# TriggerAndCVs_connectors.net
KiCad netlist of a schematic drawn in EAGLE
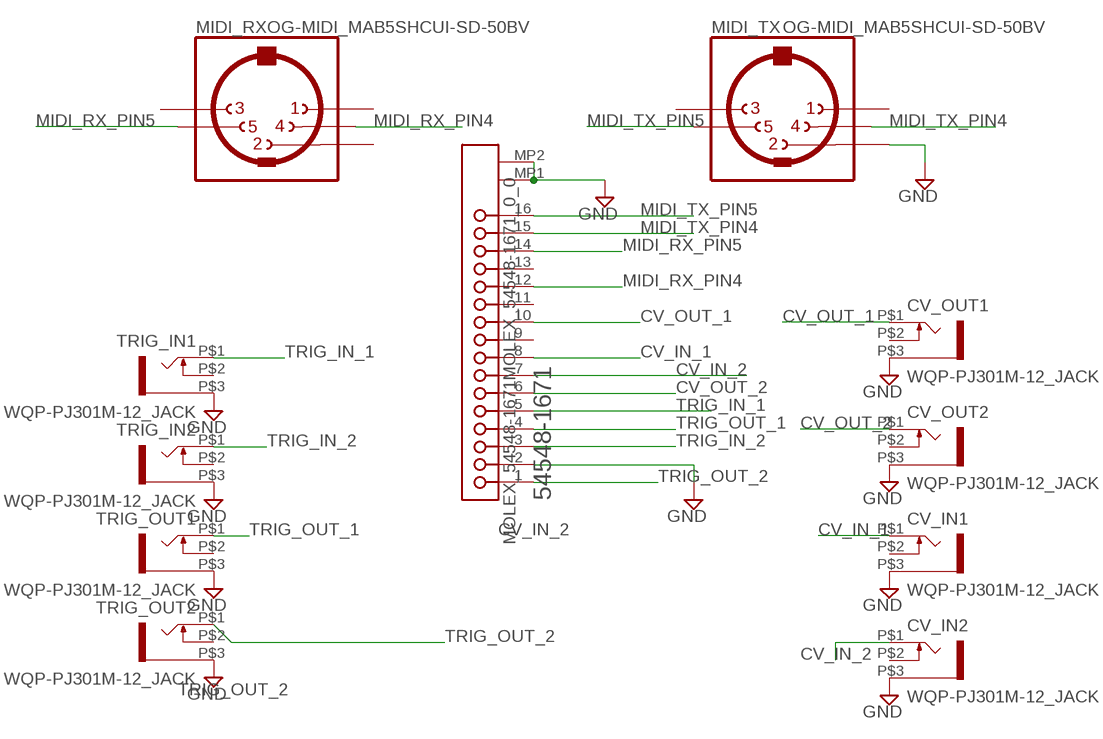
[diagram p0: schematic, sheet 1]

(export (version "E")
  (design (tool "Eeschema 10.0.6"))
  (components
    (comp (ref "CV_IN1")
      (value "WQP-PJ301M-12_JACK")
      (footprint "eagle-import:WQP-PJ301M-12_JACK")
      (libsource (lib "eagle-import") (part "WQP-PJ301M-12_JACK"))
    )
    (comp (ref "CV_IN2")
      (value "WQP-PJ301M-12_JACK")
      (footprint "eagle-import:WQP-PJ301M-12_JACK")
      (libsource (lib "eagle-import") (part "WQP-PJ301M-12_JACK"))
    )
    (comp (ref "CV_OUT1")
      (value "WQP-PJ301M-12_JACK")
      (footprint "eagle-import:WQP-PJ301M-12_JACK")
      (libsource (lib "eagle-import") (part "WQP-PJ301M-12_JACK"))
    )
    (comp (ref "CV_OUT2")
      (value "WQP-PJ301M-12_JACK")
      (footprint "eagle-import:WQP-PJ301M-12_JACK")
      (libsource (lib "eagle-import") (part "WQP-PJ301M-12_JACK"))
    )
    (comp (ref "JP4")
      (value "MOLEX_54548-1671MOLEX_54548-1671_0_0")
      (footprint "eagle-import:MOLEX_54548-1671_0")
      (fields (field (name "MF") "Molex") (field (name "MPN") "54548-1671"))
      (libsource (lib "eagle-import") (part "MOLEX_54548-1671MOLEX_54548-1671_0_0"))
    )
    (comp (ref "MIDI_RX")
      (value "OG-MIDI_MAB5SHCUI-SD-50BV")
      (footprint "eagle-import:OG-MIDI_SD-50BV")
      (libsource (lib "eagle-import") (part "OG-MIDI_MAB5SHCUI-SD-50BV"))
    )
    (comp (ref "MIDI_TX")
      (value "OG-MIDI_MAB5SHCUI-SD-50BV")
      (footprint "eagle-import:OG-MIDI_SD-50BV")
      (libsource (lib "eagle-import") (part "OG-MIDI_MAB5SHCUI-SD-50BV"))
    )
    (comp (ref "TRIG_IN1")
      (value "WQP-PJ301M-12_JACK")
      (footprint "eagle-import:WQP-PJ301M-12_JACK")
      (libsource (lib "eagle-import") (part "WQP-PJ301M-12_JACK"))
    )
    (comp (ref "TRIG_IN2")
      (value "WQP-PJ301M-12_JACK")
      (footprint "eagle-import:WQP-PJ301M-12_JACK")
      (libsource (lib "eagle-import") (part "WQP-PJ301M-12_JACK"))
    )
    (comp (ref "TRIG_OUT1")
      (value "WQP-PJ301M-12_JACK")
      (footprint "eagle-import:WQP-PJ301M-12_JACK")
      (libsource (lib "eagle-import") (part "WQP-PJ301M-12_JACK"))
    )
    (comp (ref "TRIG_OUT2")
      (value "WQP-PJ301M-12_JACK")
      (footprint "eagle-import:WQP-PJ301M-12_JACK")
      (libsource (lib "eagle-import") (part "WQP-PJ301M-12_JACK"))
    )
  )
  (nets
    (net (code "1") (name "/CV_IN_1") (class "Default")
      (node (ref "CV_IN1") (pin "P$1") (pinfunction "2_P$1") (pintype "passive"))
      (node (ref "JP4") (pin "8") (pinfunction "8_8") (pintype "passive"))
    )
    (net (code "2") (name "/CV_IN_2") (class "Default")
      (node (ref "CV_IN2") (pin "P$1") (pinfunction "2_P$1") (pintype "passive"))
      (node (ref "JP4") (pin "7") (pinfunction "7_7") (pintype "passive"))
    )
    (net (code "3") (name "/CV_OUT_1") (class "Default")
      (node (ref "CV_OUT1") (pin "P$1") (pinfunction "2_P$1") (pintype "passive"))
      (node (ref "JP4") (pin "10") (pinfunction "10_10") (pintype "passive"))
    )
    (net (code "4") (name "/CV_OUT_2") (class "Default")
      (node (ref "CV_OUT2") (pin "P$1") (pinfunction "2_P$1") (pintype "passive"))
      (node (ref "JP4") (pin "6") (pinfunction "6_6") (pintype "passive"))
    )
    (net (code "5") (name "/MIDI_RX_PIN4") (class "Default")
      (node (ref "JP4") (pin "12") (pinfunction "12_12") (pintype "passive"))
      (node (ref "MIDI_RX") (pin "4") (pinfunction "4_4") (pintype "passive"))
    )
    (net (code "6") (name "/MIDI_RX_PIN5") (class "Default")
      (node (ref "JP4") (pin "14") (pinfunction "14_14") (pintype "passive"))
      (node (ref "MIDI_RX") (pin "5") (pinfunction "5_5") (pintype "passive"))
    )
    (net (code "7") (name "/MIDI_TX_PIN4") (class "Default")
      (node (ref "JP4") (pin "15") (pinfunction "15_15") (pintype "passive"))
      (node (ref "MIDI_TX") (pin "4") (pinfunction "4_4") (pintype "passive"))
    )
    (net (code "8") (name "/MIDI_TX_PIN5") (class "Default")
      (node (ref "JP4") (pin "16") (pinfunction "16_16") (pintype "passive"))
      (node (ref "MIDI_TX") (pin "5") (pinfunction "5_5") (pintype "passive"))
    )
    (net (code "9") (name "/TRIG_IN_1") (class "Default")
      (node (ref "JP4") (pin "5") (pinfunction "5_5") (pintype "passive"))
      (node (ref "TRIG_IN1") (pin "P$1") (pinfunction "2_P$1") (pintype "passive"))
    )
    (net (code "10") (name "/TRIG_IN_2") (class "Default")
      (node (ref "JP4") (pin "3") (pinfunction "3_3") (pintype "passive"))
      (node (ref "TRIG_IN2") (pin "P$1") (pinfunction "2_P$1") (pintype "passive"))
    )
    (net (code "11") (name "/TRIG_OUT_1") (class "Default")
      (node (ref "JP4") (pin "4") (pinfunction "4_4") (pintype "passive"))
      (node (ref "TRIG_OUT1") (pin "P$1") (pinfunction "2_P$1") (pintype "passive"))
    )
    (net (code "12") (name "/TRIG_OUT_2") (class "Default")
      (node (ref "JP4") (pin "1") (pinfunction "1_1") (pintype "passive"))
      (node (ref "TRIG_OUT2") (pin "P$1") (pinfunction "2_P$1") (pintype "passive"))
    )
    (net (code "13") (name "GND") (class "Default")
      (node (ref "CV_IN1") (pin "P$3") (pinfunction "1_P$3") (pintype "passive"))
      (node (ref "CV_IN2") (pin "P$3") (pinfunction "1_P$3") (pintype "passive"))
      (node (ref "CV_OUT1") (pin "P$3") (pinfunction "1_P$3") (pintype "passive"))
      (node (ref "CV_OUT2") (pin "P$3") (pinfunction "1_P$3") (pintype "passive"))
      (node (ref "JP4") (pin "2") (pinfunction "2_2") (pintype "passive"))
      (node (ref "JP4") (pin "MP1") (pinfunction "MP1_MP1") (pintype "passive"))
      (node (ref "JP4") (pin "MP2") (pinfunction "MP2_MP2") (pintype "passive"))
      (node (ref "MIDI_TX") (pin "2") (pinfunction "2_2") (pintype "passive"))
      (node (ref "TRIG_IN1") (pin "P$3") (pinfunction "1_P$3") (pintype "passive"))
      (node (ref "TRIG_IN2") (pin "P$3") (pinfunction "1_P$3") (pintype "passive"))
      (node (ref "TRIG_OUT1") (pin "P$3") (pinfunction "1_P$3") (pintype "passive"))
      (node (ref "TRIG_OUT2") (pin "P$3") (pinfunction "1_P$3") (pintype "passive"))
    )
    (net (code "14") (name "unconnected-(CV_IN1-3-PadP$2)") (class "Default")
      (node (ref "CV_IN1") (pin "P$2") (pinfunction "3_P$2") (pintype "passive"))
    )
    (net (code "15") (name "unconnected-(CV_IN2-3-PadP$2)") (class "Default")
      (node (ref "CV_IN2") (pin "P$2") (pinfunction "3_P$2") (pintype "passive"))
    )
    (net (code "16") (name "unconnected-(CV_OUT1-3-PadP$2)") (class "Default")
      (node (ref "CV_OUT1") (pin "P$2") (pinfunction "3_P$2") (pintype "passive"))
    )
    (net (code "17") (name "unconnected-(CV_OUT2-3-PadP$2)") (class "Default")
      (node (ref "CV_OUT2") (pin "P$2") (pinfunction "3_P$2") (pintype "passive"))
    )
    (net (code "18") (name "unconnected-(JP4-Pad9)") (class "Default")
      (node (ref "JP4") (pin "9") (pinfunction "9_9") (pintype "passive"))
    )
    (net (code "19") (name "unconnected-(JP4-Pad11)") (class "Default")
      (node (ref "JP4") (pin "11") (pinfunction "11_11") (pintype "passive"))
    )
    (net (code "20") (name "unconnected-(JP4-Pad13)") (class "Default")
      (node (ref "JP4") (pin "13") (pinfunction "13_13") (pintype "passive"))
    )
    (net (code "21") (name "unconnected-(MIDI_RX-Pad1)") (class "Default")
      (node (ref "MIDI_RX") (pin "1") (pinfunction "1_1") (pintype "passive"))
    )
    (net (code "22") (name "unconnected-(MIDI_RX-Pad2)") (class "Default")
      (node (ref "MIDI_RX") (pin "2") (pinfunction "2_2") (pintype "passive"))
    )
    (net (code "23") (name "unconnected-(MIDI_RX-Pad3)") (class "Default")
      (node (ref "MIDI_RX") (pin "3") (pinfunction "3_3") (pintype "passive"))
    )
    (net (code "24") (name "unconnected-(MIDI_TX-Pad1)") (class "Default")
      (node (ref "MIDI_TX") (pin "1") (pinfunction "1_1") (pintype "passive"))
    )
    (net (code "25") (name "unconnected-(MIDI_TX-Pad3)") (class "Default")
      (node (ref "MIDI_TX") (pin "3") (pinfunction "3_3") (pintype "passive"))
    )
    (net (code "26") (name "unconnected-(TRIG_IN1-3-PadP$2)") (class "Default")
      (node (ref "TRIG_IN1") (pin "P$2") (pinfunction "3_P$2") (pintype "passive"))
    )
    (net (code "27") (name "unconnected-(TRIG_IN2-3-PadP$2)") (class "Default")
      (node (ref "TRIG_IN2") (pin "P$2") (pinfunction "3_P$2") (pintype "passive"))
    )
    (net (code "28") (name "unconnected-(TRIG_OUT1-3-PadP$2)") (class "Default")
      (node (ref "TRIG_OUT1") (pin "P$2") (pinfunction "3_P$2") (pintype "passive"))
    )
    (net (code "29") (name "unconnected-(TRIG_OUT2-3-PadP$2)") (class "Default")
      (node (ref "TRIG_OUT2") (pin "P$2") (pinfunction "3_P$2") (pintype "passive"))
    )
  )
)
